# Sheet1.net
KiCad netlist of a schematic drawn in Altium Designer
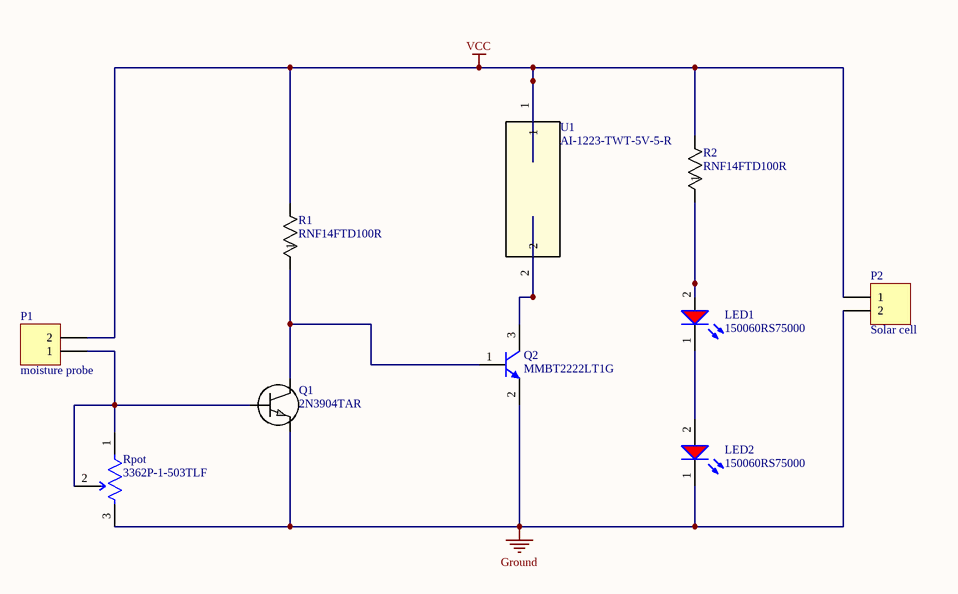
[diagram p0: Sheet1.SchDoc]

(export (version "E")
  (design (tool "Eeschema 10.0.6"))
  (components
    (comp (ref "LED1")
      (value "150060RS75000")
      (footprint "WL-SMCW_0603_150060xx75000")
      (libsource (lib "Altium Content Vault") (part "LED_Red_2A-1K"))
    )
    (comp (ref "LED2")
      (value "150060RS75000")
      (footprint "WL-SMCW_0603_150060xx75000")
      (libsource (lib "Altium Content Vault") (part "LED_Red_2A-1K"))
    )
    (comp (ref "P1")
      (value "moisture probe")
      (footprint "HDR1X2")
      (description "Header, 2-Pin")
      (fields (field (name "PUBLISHER") "Altium Limited"))
      (libsource (lib "") (part "Header 2_1"))
    )
    (comp (ref "P2")
      (value "Solar cell")
      (footprint "HDR1X2")
      (description "Header, 2-Pin")
      (fields (field (name "PUBLISHER") "Altium Limited"))
      (libsource (lib "Miscellaneous Connectors") (part "Header 2"))
    )
    (comp (ref "Q1")
      (value "2N3904TAR")
      (footprint "TO-92-3_135AR_ONS")
      (description "No Description Available")
      (fields (field (name "COPYRIGHT") "Copyright (C) 2024 Ultra Librarian. All rights reserved."))
      (libsource (lib "2N3904TAR") (part "2N3904TAR"))
    )
    (comp (ref "Q2")
      (value "MMBT2222LT1G")
      (footprint "ONSC-SOT-23-3-318-08_V")
      (description "General Purpose Transistor, NPN Silicon, 3-Pin SOT-23, Pb-Free, Tape and Reel")
      (fields (field (name "MANUFACTURER") "On Semiconductor"))
      (libsource (lib "Altium Content Vault") (part "ONSC-NPN-B1E2C3-3"))
    )
    (comp (ref "R1")
      (value "RNF14FTD100R")
      (footprint "STA_RNF14_STP")
      (description "No Description Available")
      (fields (field (name "COPYRIGHT") "Copyright (C) 2024 Ultra Librarian. All rights reserved."))
      (libsource (lib "2N3904TAR") (part "RNF14FTD100R"))
    )
    (comp (ref "R2")
      (value "RNF14FTD100R")
      (footprint "STA_RNF14_STP")
      (description "No Description Available")
      (fields (field (name "COPYRIGHT") "Copyright (C) 2024 Ultra Librarian. All rights reserved."))
      (libsource (lib "2N3904TAR") (part "RNF14FTD100R"))
    )
    (comp (ref "Rpot")
      (value "3362P-1-503TLF")
      (footprint "FP-3362P-1-503TLF-MFG")
      (description "TRIMMER 50K OHM 0.5W PC PIN TOP")
      (fields (field (name "TOLERANCE") "10%"))
      (libsource (lib "Altium Content Vault") (part "2dcfd2547301a7d3209a5e99acfd772"))
    )
    (comp (ref "U1")
      (value "AI-1223-TWT-5V-5-R")
      (footprint "AI-1223-TWT-5V-5-R_PUI")
      (description "No Description Available")
      (fields (field (name "COPYRIGHT") "Copyright (C) 2024 Ultra Librarian. All rights reserved."))
      (libsource (lib "2N3904TAR") (part "AI-1223-TWT-5V-5-R"))
    )
  )
  (nets
    (net (code "1") (name "Ground") (class "Default")
      (node (ref "LED2") (pin "1") (pinfunction "K_1") (pintype "passive"))
      (node (ref "P2") (pin "2") (pinfunction "2_2") (pintype "passive"))
      (node (ref "Q1") (pin "1") (pinfunction "E_1") (pintype "passive"))
      (node (ref "Q2") (pin "2") (pinfunction "E_2") (pintype "passive"))
      (node (ref "Rpot") (pin "3") (pinfunction "CW_3") (pintype "passive"))
    )
    (net (code "2") (name "Net-(LED1-A)") (class "Default")
      (node (ref "LED1") (pin "2") (pinfunction "A_2") (pintype "passive"))
      (node (ref "R2") (pin "1") (pinfunction "1_1") (pintype "passive"))
    )
    (net (code "3") (name "Net-(LED1-K)") (class "Default")
      (node (ref "LED1") (pin "1") (pinfunction "K_1") (pintype "passive"))
      (node (ref "LED2") (pin "2") (pinfunction "A_2") (pintype "passive"))
    )
    (net (code "4") (name "Net-(Q1-B)") (class "Default")
      (node (ref "P1") (pin "1") (pinfunction "1_1") (pintype "passive"))
      (node (ref "Q1") (pin "2") (pinfunction "B_2") (pintype "passive"))
      (node (ref "Rpot") (pin "1") (pinfunction "CCW_1") (pintype "passive"))
      (node (ref "Rpot") (pin "2") (pinfunction "WIPER_2") (pintype "passive"))
    )
    (net (code "5") (name "Net-(Q1-C)") (class "Default")
      (node (ref "Q1") (pin "3") (pinfunction "C_3") (pintype "passive"))
      (node (ref "Q2") (pin "1") (pinfunction "B_1") (pintype "passive"))
      (node (ref "R1") (pin "1") (pinfunction "1_1") (pintype "passive"))
    )
    (net (code "6") (name "Net-(Q2-C)") (class "Default")
      (node (ref "Q2") (pin "3") (pinfunction "C_3") (pintype "passive"))
      (node (ref "U1") (pin "2") (pinfunction "2_2") (pintype "passive"))
    )
    (net (code "7") (name "VCC") (class "Default")
      (node (ref "P1") (pin "2") (pinfunction "2_2") (pintype "passive"))
      (node (ref "P2") (pin "1") (pinfunction "1_1") (pintype "passive"))
      (node (ref "R1") (pin "2") (pinfunction "2_2") (pintype "passive"))
      (node (ref "R2") (pin "2") (pinfunction "2_2") (pintype "passive"))
      (node (ref "U1") (pin "1") (pinfunction "1_1") (pintype "passive"))
    )
  )
)
